# Timer-Ruler_v5.net
KiCad netlist of a schematic drawn in EAGLE
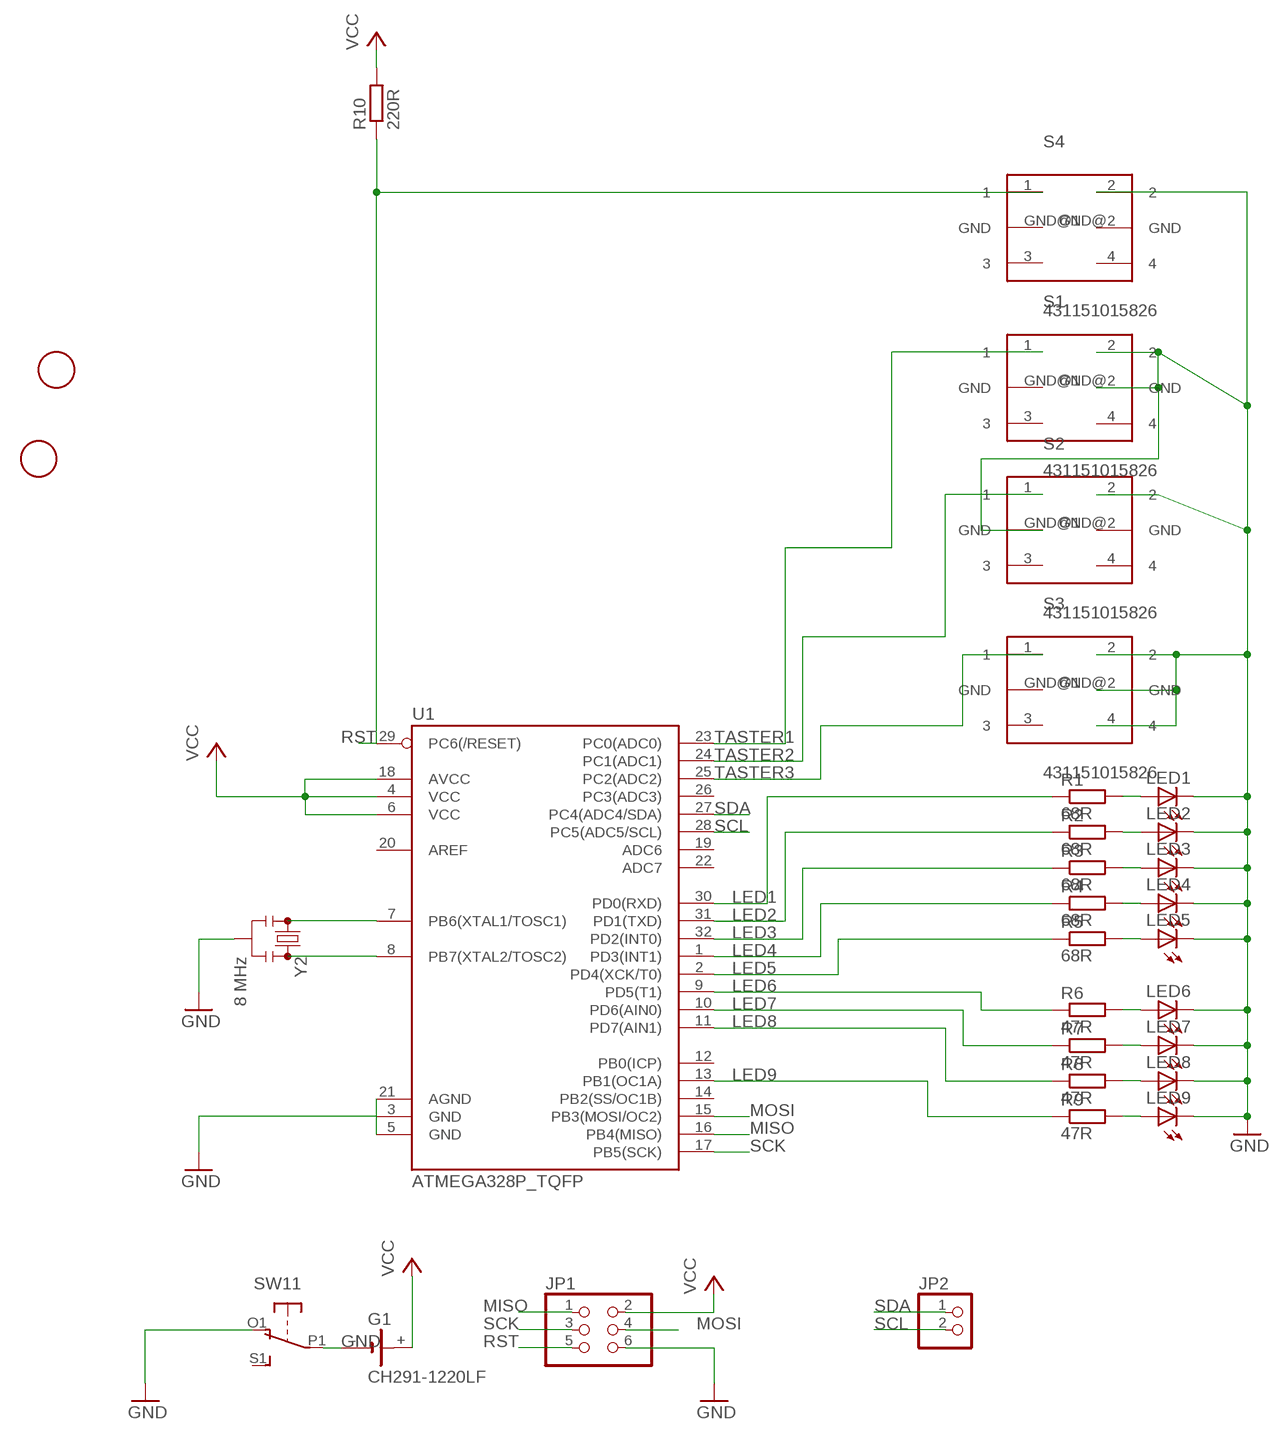
[diagram p0: schematic, sheet 1]

(export (version "E")
  (design (tool "Eeschema 10.0.6"))
  (components
    (comp (ref "G1")
      (value "CH291-1220LF")
      (footprint "eagle-import:CH291-1220LF")
      (libsource (lib "eagle-import") (part "CH291-1220LF"))
    )
    (comp (ref "JP1")
      (value "PINHD-2X3")
      (footprint "eagle-import:2X03")
      (libsource (lib "eagle-import") (part "PINHD-2X3"))
    )
    (comp (ref "JP2")
      (value "PINHD-1X2")
      (footprint "eagle-import:1X02")
      (libsource (lib "eagle-import") (part "PINHD-1X2"))
    )
    (comp (ref "LED1")
      (value "LEDCHIP-LED0603")
      (footprint "eagle-import:CHIP-LED0603")
      (libsource (lib "eagle-import") (part "LEDCHIP-LED0603"))
    )
    (comp (ref "LED2")
      (value "LEDCHIP-LED0603")
      (footprint "eagle-import:CHIP-LED0603")
      (libsource (lib "eagle-import") (part "LEDCHIP-LED0603"))
    )
    (comp (ref "LED3")
      (value "LEDCHIP-LED0603")
      (footprint "eagle-import:CHIP-LED0603")
      (libsource (lib "eagle-import") (part "LEDCHIP-LED0603"))
    )
    (comp (ref "LED4")
      (value "LEDCHIP-LED0603")
      (footprint "eagle-import:CHIP-LED0603")
      (libsource (lib "eagle-import") (part "LEDCHIP-LED0603"))
    )
    (comp (ref "LED5")
      (value "LEDCHIP-LED0603")
      (footprint "eagle-import:CHIP-LED0603")
      (libsource (lib "eagle-import") (part "LEDCHIP-LED0603"))
    )
    (comp (ref "LED6")
      (value "LEDCHIP-LED0603")
      (footprint "eagle-import:CHIP-LED0603")
      (libsource (lib "eagle-import") (part "LEDCHIP-LED0603"))
    )
    (comp (ref "LED7")
      (value "LEDCHIP-LED0603")
      (footprint "eagle-import:CHIP-LED0603")
      (libsource (lib "eagle-import") (part "LEDCHIP-LED0603"))
    )
    (comp (ref "LED8")
      (value "LEDCHIP-LED0603")
      (footprint "eagle-import:CHIP-LED0603")
      (libsource (lib "eagle-import") (part "LEDCHIP-LED0603"))
    )
    (comp (ref "LED9")
      (value "LEDCHIP-LED0603")
      (footprint "eagle-import:CHIP-LED0603")
      (libsource (lib "eagle-import") (part "LEDCHIP-LED0603"))
    )
    (comp (ref "R1")
      (value "68R")
      (footprint "eagle-import:R0603")
      (libsource (lib "eagle-import") (part "R-EU_R0603"))
    )
    (comp (ref "R2")
      (value "68R")
      (footprint "eagle-import:R0603")
      (libsource (lib "eagle-import") (part "R-EU_R0603"))
    )
    (comp (ref "R3")
      (value "68R")
      (footprint "eagle-import:R0603")
      (libsource (lib "eagle-import") (part "R-EU_R0603"))
    )
    (comp (ref "R4")
      (value "68R")
      (footprint "eagle-import:R0603")
      (libsource (lib "eagle-import") (part "R-EU_R0603"))
    )
    (comp (ref "R5")
      (value "68R")
      (footprint "eagle-import:R0603")
      (libsource (lib "eagle-import") (part "R-EU_R0603"))
    )
    (comp (ref "R6")
      (value "47R")
      (footprint "eagle-import:R0603")
      (libsource (lib "eagle-import") (part "R-EU_R0603"))
    )
    (comp (ref "R7")
      (value "47R")
      (footprint "eagle-import:R0603")
      (libsource (lib "eagle-import") (part "R-EU_R0603"))
    )
    (comp (ref "R8")
      (value "47R")
      (footprint "eagle-import:R0603")
      (libsource (lib "eagle-import") (part "R-EU_R0603"))
    )
    (comp (ref "R9")
      (value "47R")
      (footprint "eagle-import:R0603")
      (libsource (lib "eagle-import") (part "R-EU_R0603"))
    )
    (comp (ref "R10")
      (value "220R")
      (footprint "eagle-import:R0603")
      (libsource (lib "eagle-import") (part "R-EU_R0603"))
    )
    (comp (ref "S1")
      (value "431151015826")
      (footprint "eagle-import:431181015816")
      (libsource (lib "eagle-import") (part "431151015826"))
    )
    (comp (ref "S2")
      (value "431151015826")
      (footprint "eagle-import:431181015816")
      (libsource (lib "eagle-import") (part "431151015826"))
    )
    (comp (ref "S3")
      (value "431151015826")
      (footprint "eagle-import:431181015816")
      (libsource (lib "eagle-import") (part "431151015826"))
    )
    (comp (ref "S4")
      (value "431151015826")
      (footprint "eagle-import:431181015816")
      (libsource (lib "eagle-import") (part "431151015826"))
    )
    (comp (ref "SW1")
      (value "DPDT-EG1390")
      (footprint "eagle-import:EG1390")
      (libsource (lib "eagle-import") (part "DPDT-EG1390"))
    )
    (comp (ref "U$1")
      (value "FIDUCIAL")
      (footprint "eagle-import:FIDUCIAL_1MM")
      (libsource (lib "eagle-import") (part "FIDUCIAL"))
    )
    (comp (ref "U$2")
      (value "FIDUCIAL")
      (footprint "eagle-import:FIDUCIAL_1MM")
      (libsource (lib "eagle-import") (part "FIDUCIAL"))
    )
    (comp (ref "U1")
      (value "ATMEGA328P_TQFP")
      (footprint "eagle-import:TQFP32-08")
      (libsource (lib "eagle-import") (part "ATMEGA328P_TQFP"))
    )
    (comp (ref "Y2")
      (value "8 MHz")
      (footprint "eagle-import:RESONATOR-SMD")
      (libsource (lib "eagle-import") (part "RESONATOR8MHZ"))
    )
  )
  (nets
    (net (code "1") (name "/LED1") (class "Default")
      (node (ref "R1") (pin "1") (pinfunction "1_1") (pintype "passive"))
      (node (ref "U1") (pin "30") (pinfunction "PD0(RXD)_30") (pintype "bidirectional"))
    )
    (net (code "2") (name "/LED2") (class "Default")
      (node (ref "R2") (pin "1") (pinfunction "1_1") (pintype "passive"))
      (node (ref "U1") (pin "31") (pinfunction "PD1(TXD)_31") (pintype "bidirectional"))
    )
    (net (code "3") (name "/LED3") (class "Default")
      (node (ref "R3") (pin "1") (pinfunction "1_1") (pintype "passive"))
      (node (ref "U1") (pin "32") (pinfunction "PD2(INT0)_32") (pintype "bidirectional"))
    )
    (net (code "4") (name "/LED4") (class "Default")
      (node (ref "R4") (pin "1") (pinfunction "1_1") (pintype "passive"))
      (node (ref "U1") (pin "1") (pinfunction "PD3(INT1)_1") (pintype "bidirectional"))
    )
    (net (code "5") (name "/LED5") (class "Default")
      (node (ref "R5") (pin "1") (pinfunction "1_1") (pintype "passive"))
      (node (ref "U1") (pin "2") (pinfunction "PD4(XCK/T0)_2") (pintype "bidirectional"))
    )
    (net (code "6") (name "/LED6") (class "Default")
      (node (ref "R6") (pin "1") (pinfunction "1_1") (pintype "passive"))
      (node (ref "U1") (pin "9") (pinfunction "PD5(T1)_9") (pintype "bidirectional"))
    )
    (net (code "7") (name "/LED7") (class "Default")
      (node (ref "R7") (pin "1") (pinfunction "1_1") (pintype "passive"))
      (node (ref "U1") (pin "10") (pinfunction "PD6(AIN0)_10") (pintype "bidirectional"))
    )
    (net (code "8") (name "/LED8") (class "Default")
      (node (ref "R8") (pin "1") (pinfunction "1_1") (pintype "passive"))
      (node (ref "U1") (pin "11") (pinfunction "PD7(AIN1)_11") (pintype "bidirectional"))
    )
    (net (code "9") (name "/LED9") (class "Default")
      (node (ref "R9") (pin "1") (pinfunction "1_1") (pintype "passive"))
      (node (ref "U1") (pin "13") (pinfunction "PB1(OC1A)_13") (pintype "bidirectional"))
    )
    (net (code "10") (name "/MISO") (class "Default")
      (node (ref "JP1") (pin "1") (pinfunction "1_1") (pintype "passive"))
      (node (ref "U1") (pin "16") (pinfunction "PB4(MISO)_16") (pintype "bidirectional"))
    )
    (net (code "11") (name "/MOSI") (class "Default")
      (node (ref "JP1") (pin "4") (pinfunction "4_4") (pintype "passive"))
      (node (ref "U1") (pin "15") (pinfunction "PB3(MOSI/OC2)_15") (pintype "bidirectional"))
    )
    (net (code "12") (name "/RST") (class "Default")
      (node (ref "JP1") (pin "5") (pinfunction "5_5") (pintype "passive"))
      (node (ref "R10") (pin "1") (pinfunction "1_1") (pintype "passive"))
      (node (ref "S4") (pin "1") (pinfunction "1_1") (pintype "bidirectional"))
      (node (ref "U1") (pin "29") (pinfunction "PC6(/RESET)_29") (pintype "bidirectional"))
    )
    (net (code "13") (name "/SCK") (class "Default")
      (node (ref "JP1") (pin "3") (pinfunction "3_3") (pintype "passive"))
      (node (ref "U1") (pin "17") (pinfunction "PB5(SCK)_17") (pintype "bidirectional"))
    )
    (net (code "14") (name "/SCL") (class "Default")
      (node (ref "JP2") (pin "2") (pinfunction "2_2") (pintype "passive"))
      (node (ref "U1") (pin "28") (pinfunction "PC5(ADC5/SCL)_28") (pintype "bidirectional"))
    )
    (net (code "15") (name "/SDA") (class "Default")
      (node (ref "JP2") (pin "1") (pinfunction "1_1") (pintype "passive"))
      (node (ref "U1") (pin "27") (pinfunction "PC4(ADC4/SDA)_27") (pintype "bidirectional"))
    )
    (net (code "16") (name "/TASTER1") (class "Default")
      (node (ref "S1") (pin "1") (pinfunction "1_1") (pintype "bidirectional"))
      (node (ref "U1") (pin "23") (pinfunction "PC0(ADC0)_23") (pintype "bidirectional"))
    )
    (net (code "17") (name "/TASTER2") (class "Default")
      (node (ref "S2") (pin "1") (pinfunction "1_1") (pintype "bidirectional"))
      (node (ref "U1") (pin "24") (pinfunction "PC1(ADC1)_24") (pintype "bidirectional"))
    )
    (net (code "18") (name "/TASTER3") (class "Default")
      (node (ref "S3") (pin "1") (pinfunction "1_1") (pintype "bidirectional"))
      (node (ref "U1") (pin "25") (pinfunction "PC2(ADC2)_25") (pintype "bidirectional"))
    )
    (net (code "19") (name "GND") (class "Default")
      (node (ref "G1") (pin "-") (pinfunction "-_-") (pintype "passive"))
      (node (ref "JP1") (pin "6") (pinfunction "6_6") (pintype "passive"))
      (node (ref "LED1") (pin "C") (pinfunction "C_C") (pintype "passive"))
      (node (ref "LED2") (pin "C") (pinfunction "C_C") (pintype "passive"))
      (node (ref "LED3") (pin "C") (pinfunction "C_C") (pintype "passive"))
      (node (ref "LED4") (pin "C") (pinfunction "C_C") (pintype "passive"))
      (node (ref "LED5") (pin "C") (pinfunction "C_C") (pintype "passive"))
      (node (ref "LED6") (pin "C") (pinfunction "C_C") (pintype "passive"))
      (node (ref "LED7") (pin "C") (pinfunction "C_C") (pintype "passive"))
      (node (ref "LED8") (pin "C") (pinfunction "C_C") (pintype "passive"))
      (node (ref "LED9") (pin "C") (pinfunction "C_C") (pintype "passive"))
      (node (ref "S1") (pin "2") (pinfunction "2_2") (pintype "bidirectional"))
      (node (ref "S1") (pin "GND@2") (pinfunction "GND_GND@2") (pintype "bidirectional"))
      (node (ref "S2") (pin "2") (pinfunction "2_2") (pintype "bidirectional"))
      (node (ref "S2") (pin "GND@1") (pinfunction "GND_GND@1") (pintype "bidirectional"))
      (node (ref "S3") (pin "2") (pinfunction "2_2") (pintype "bidirectional"))
      (node (ref "S3") (pin "4") (pinfunction "4_4") (pintype "bidirectional"))
      (node (ref "S3") (pin "GND@2") (pinfunction "GND_GND@2") (pintype "bidirectional"))
      (node (ref "S4") (pin "2") (pinfunction "2_2") (pintype "bidirectional"))
      (node (ref "SW1") (pin "O1") (pinfunction "O_O1") (pintype "passive"))
      (node (ref "SW1") (pin "P1") (pinfunction "P_P1") (pintype "passive"))
      (node (ref "U1") (pin "3") (pinfunction "GND_3") (pintype "bidirectional"))
      (node (ref "Y2") (pin "2") (pinfunction "2_2") (pintype "passive"))
    )
    (net (code "20") (name "Net-(LED1-PadA)") (class "Default")
      (node (ref "LED1") (pin "A") (pinfunction "A_A") (pintype "passive"))
      (node (ref "R1") (pin "2") (pinfunction "2_2") (pintype "passive"))
    )
    (net (code "21") (name "Net-(LED2-PadA)") (class "Default")
      (node (ref "LED2") (pin "A") (pinfunction "A_A") (pintype "passive"))
      (node (ref "R2") (pin "2") (pinfunction "2_2") (pintype "passive"))
    )
    (net (code "22") (name "Net-(LED3-PadA)") (class "Default")
      (node (ref "LED3") (pin "A") (pinfunction "A_A") (pintype "passive"))
      (node (ref "R3") (pin "2") (pinfunction "2_2") (pintype "passive"))
    )
    (net (code "23") (name "Net-(LED4-PadA)") (class "Default")
      (node (ref "LED4") (pin "A") (pinfunction "A_A") (pintype "passive"))
      (node (ref "R4") (pin "2") (pinfunction "2_2") (pintype "passive"))
    )
    (net (code "24") (name "Net-(LED5-PadA)") (class "Default")
      (node (ref "LED5") (pin "A") (pinfunction "A_A") (pintype "passive"))
      (node (ref "R5") (pin "2") (pinfunction "2_2") (pintype "passive"))
    )
    (net (code "25") (name "Net-(LED6-PadA)") (class "Default")
      (node (ref "LED6") (pin "A") (pinfunction "A_A") (pintype "passive"))
      (node (ref "R6") (pin "2") (pinfunction "2_2") (pintype "passive"))
    )
    (net (code "26") (name "Net-(LED7-PadA)") (class "Default")
      (node (ref "LED7") (pin "A") (pinfunction "A_A") (pintype "passive"))
      (node (ref "R7") (pin "2") (pinfunction "2_2") (pintype "passive"))
    )
    (net (code "27") (name "Net-(LED8-PadA)") (class "Default")
      (node (ref "LED8") (pin "A") (pinfunction "A_A") (pintype "passive"))
      (node (ref "R8") (pin "2") (pinfunction "2_2") (pintype "passive"))
    )
    (net (code "28") (name "Net-(LED9-PadA)") (class "Default")
      (node (ref "LED9") (pin "A") (pinfunction "A_A") (pintype "passive"))
      (node (ref "R9") (pin "2") (pinfunction "2_2") (pintype "passive"))
    )
    (net (code "29") (name "Net-(U1-AGND)") (class "Default")
      (node (ref "U1") (pin "21") (pinfunction "AGND_21") (pintype "bidirectional"))
      (node (ref "U1") (pin "5") (pinfunction "GND_5") (pintype "bidirectional"))
    )
    (net (code "30") (name "Net-(U1-PB6(XTAL1{slash}TOSC1))") (class "Default")
      (node (ref "U1") (pin "7") (pinfunction "PB6(XTAL1/TOSC1)_7") (pintype "bidirectional"))
      (node (ref "Y2") (pin "1") (pinfunction "1_1") (pintype "passive"))
    )
    (net (code "31") (name "Net-(U1-PB7(XTAL2{slash}TOSC2))") (class "Default")
      (node (ref "U1") (pin "8") (pinfunction "PB7(XTAL2/TOSC2)_8") (pintype "bidirectional"))
      (node (ref "Y2") (pin "3") (pinfunction "3_3") (pintype "passive"))
    )
    (net (code "32") (name "VCC") (class "Default")
      (node (ref "G1") (pin "+") (pinfunction "+_+") (pintype "passive"))
      (node (ref "JP1") (pin "2") (pinfunction "2_2") (pintype "passive"))
      (node (ref "R10") (pin "2") (pinfunction "2_2") (pintype "passive"))
      (node (ref "U1") (pin "18") (pinfunction "AVCC_18") (pintype "bidirectional"))
      (node (ref "U1") (pin "4") (pinfunction "VCC_4") (pintype "bidirectional"))
      (node (ref "U1") (pin "6") (pinfunction "VCC_6") (pintype "bidirectional"))
    )
    (net (code "33") (name "unconnected-(S1-GND-PadGND@1)") (class "Default")
      (node (ref "S1") (pin "GND@1") (pinfunction "GND_GND@1") (pintype "bidirectional"))
    )
    (net (code "34") (name "unconnected-(S1-Pad3)") (class "Default")
      (node (ref "S1") (pin "3") (pinfunction "3_3") (pintype "bidirectional"))
    )
    (net (code "35") (name "unconnected-(S1-Pad4)") (class "Default")
      (node (ref "S1") (pin "4") (pinfunction "4_4") (pintype "bidirectional"))
    )
    (net (code "36") (name "unconnected-(S2-GND-PadGND@2)") (class "Default")
      (node (ref "S2") (pin "GND@2") (pinfunction "GND_GND@2") (pintype "bidirectional"))
    )
    (net (code "37") (name "unconnected-(S2-Pad3)") (class "Default")
      (node (ref "S2") (pin "3") (pinfunction "3_3") (pintype "bidirectional"))
    )
    (net (code "38") (name "unconnected-(S2-Pad4)") (class "Default")
      (node (ref "S2") (pin "4") (pinfunction "4_4") (pintype "bidirectional"))
    )
    (net (code "39") (name "unconnected-(S3-GND-PadGND@1)") (class "Default")
      (node (ref "S3") (pin "GND@1") (pinfunction "GND_GND@1") (pintype "bidirectional"))
    )
    (net (code "40") (name "unconnected-(S3-Pad3)") (class "Default")
      (node (ref "S3") (pin "3") (pinfunction "3_3") (pintype "bidirectional"))
    )
    (net (code "41") (name "unconnected-(S4-GND-PadGND@1)") (class "Default")
      (node (ref "S4") (pin "GND@1") (pinfunction "GND_GND@1") (pintype "bidirectional"))
    )
    (net (code "42") (name "unconnected-(S4-GND-PadGND@2)") (class "Default")
      (node (ref "S4") (pin "GND@2") (pinfunction "GND_GND@2") (pintype "bidirectional"))
    )
    (net (code "43") (name "unconnected-(S4-Pad3)") (class "Default")
      (node (ref "S4") (pin "3") (pinfunction "3_3") (pintype "bidirectional"))
    )
    (net (code "44") (name "unconnected-(S4-Pad4)") (class "Default")
      (node (ref "S4") (pin "4") (pinfunction "4_4") (pintype "bidirectional"))
    )
    (net (code "45") (name "unconnected-(SW1A-S-PadS1)") (class "Default")
      (node (ref "SW1") (pin "S1") (pinfunction "S_S1") (pintype "passive"))
    )
    (net (code "46") (name "unconnected-(U1-ADC6-Pad19)") (class "Default")
      (node (ref "U1") (pin "19") (pinfunction "ADC6_19") (pintype "bidirectional"))
    )
    (net (code "47") (name "unconnected-(U1-ADC7-Pad22)") (class "Default")
      (node (ref "U1") (pin "22") (pinfunction "ADC7_22") (pintype "bidirectional"))
    )
    (net (code "48") (name "unconnected-(U1-AREF-Pad20)") (class "Default")
      (node (ref "U1") (pin "20") (pinfunction "AREF_20") (pintype "bidirectional"))
    )
    (net (code "49") (name "unconnected-(U1-PB0(ICP)-Pad12)") (class "Default")
      (node (ref "U1") (pin "12") (pinfunction "PB0(ICP)_12") (pintype "bidirectional"))
    )
    (net (code "50") (name "unconnected-(U1-PB2(SS{slash}OC1B)-Pad14)") (class "Default")
      (node (ref "U1") (pin "14") (pinfunction "PB2(SS/OC1B)_14") (pintype "bidirectional"))
    )
    (net (code "51") (name "unconnected-(U1-PC3(ADC3)-Pad26)") (class "Default")
      (node (ref "U1") (pin "26") (pinfunction "PC3(ADC3)_26") (pintype "bidirectional"))
    )
  )
)
